# shield.net
KiCad netlist of a schematic drawn in EAGLE
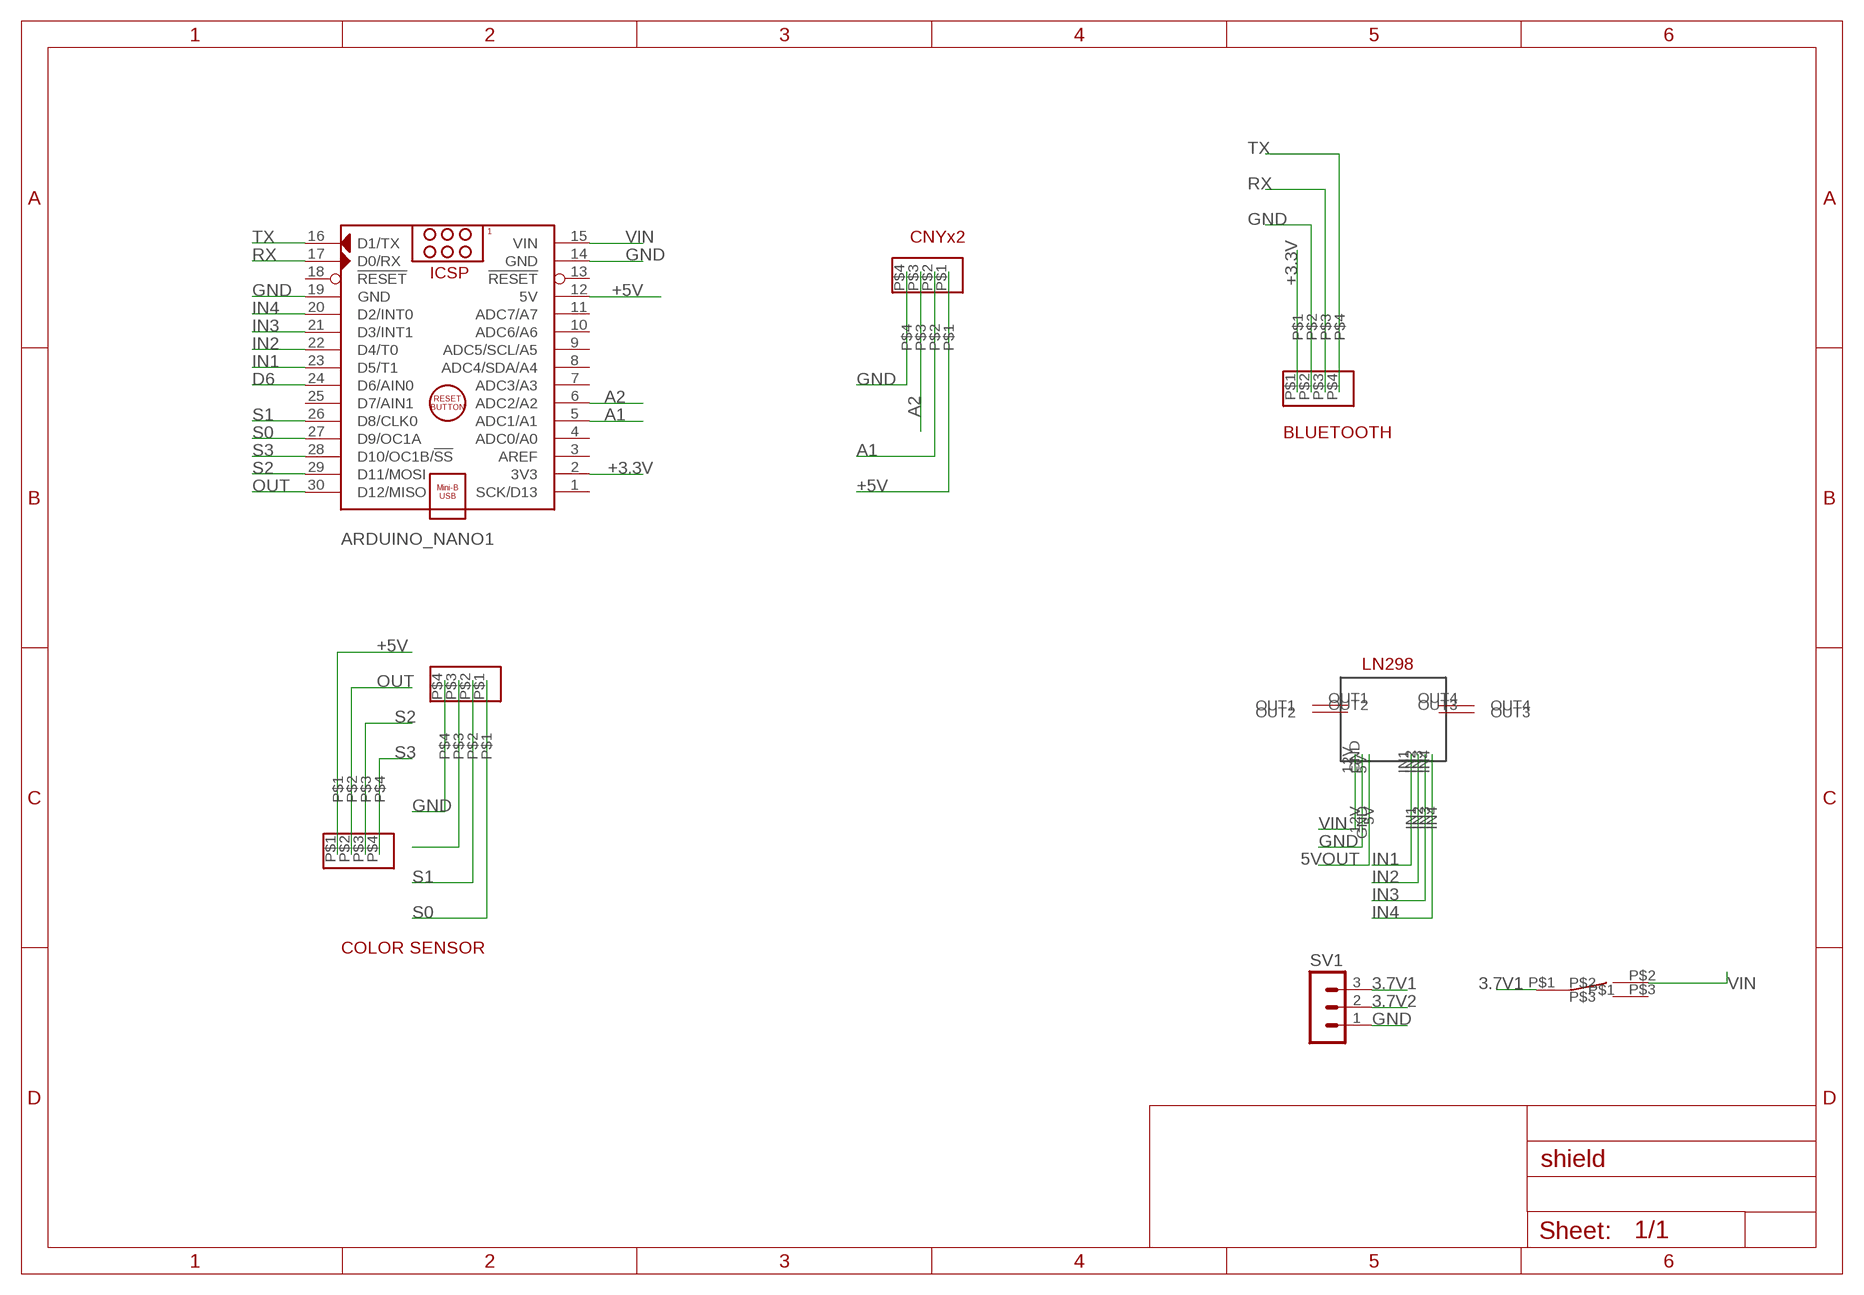
[diagram p0: schematic, sheet 1]

(export (version "E")
  (design (tool "Eeschema 10.0.6"))
  (components
    (comp (ref "ARDUINO_NANO1")
      (value "ARDUINO_NANO")
      (footprint "eagle-import:ARDUINO_NANO")
      (libsource (lib "eagle-import") (part "ARDUINO_NANO"))
    )
    (comp (ref "SV1")
      (value "MA03-1")
      (footprint "eagle-import:MA03-1")
      (libsource (lib "eagle-import") (part "MA03-1"))
    )
    (comp (ref "U$1")
      (value "PIN4")
      (footprint "eagle-import:PIN4")
      (libsource (lib "eagle-import") (part "PIN4"))
    )
    (comp (ref "U$2")
      (value "PIN4")
      (footprint "eagle-import:PIN4")
      (libsource (lib "eagle-import") (part "PIN4"))
    )
    (comp (ref "U$3")
      (value "INTERRUPTOR")
      (footprint "eagle-import:INTERRUPTOR")
      (libsource (lib "eagle-import") (part "INTERRUPTOR"))
    )
    (comp (ref "U$4")
      (value "PIN4")
      (footprint "eagle-import:PIN4")
      (libsource (lib "eagle-import") (part "PIN4"))
    )
    (comp (ref "U$5")
      (value "LN298V2")
      (footprint "eagle-import:LN298V2")
      (libsource (lib "eagle-import") (part "LN298V2"))
    )
    (comp (ref "U$6")
      (value "PIN4")
      (footprint "eagle-import:PIN4")
      (libsource (lib "eagle-import") (part "PIN4"))
    )
  )
  (nets
    (net (code "1") (name "/+3.3V") (class "Default")
      (node (ref "ARDUINO_NANO1") (pin "2") (pinfunction "3V3_2") (pintype "output"))
      (node (ref "U$1") (pin "P$1") (pinfunction "P$1_P$1") (pintype "bidirectional"))
    )
    (net (code "2") (name "/+5V") (class "Default")
      (node (ref "ARDUINO_NANO1") (pin "12") (pinfunction "5V_12") (pintype "power_in"))
      (node (ref "U$2") (pin "P$1") (pinfunction "P$1_P$1") (pintype "bidirectional"))
      (node (ref "U$6") (pin "P$1") (pinfunction "P$1_P$1") (pintype "bidirectional"))
    )
    (net (code "3") (name "/3.7V1") (class "Default")
      (node (ref "SV1") (pin "3") (pinfunction "3_3") (pintype "passive"))
      (node (ref "U$3") (pin "P$1") (pinfunction "P$1_P$1") (pintype "bidirectional"))
    )
    (net (code "4") (name "/3.7V2") (class "Default")
      (node (ref "SV1") (pin "2") (pinfunction "2_2") (pintype "passive"))
    )
    (net (code "5") (name "/5VOUT") (class "Default")
      (node (ref "U$5") (pin "5V") (pinfunction "5V_5V") (pintype "bidirectional"))
    )
    (net (code "6") (name "/A1") (class "Default")
      (node (ref "ARDUINO_NANO1") (pin "5") (pinfunction "ADC1/A1_5") (pintype "bidirectional"))
      (node (ref "U$6") (pin "P$2") (pinfunction "P$2_P$2") (pintype "bidirectional"))
    )
    (net (code "7") (name "/A2") (class "Default")
      (node (ref "ARDUINO_NANO1") (pin "6") (pinfunction "ADC2/A2_6") (pintype "bidirectional"))
      (node (ref "U$6") (pin "P$3") (pinfunction "P$3_P$3") (pintype "bidirectional"))
    )
    (net (code "8") (name "/D6") (class "Default")
      (node (ref "ARDUINO_NANO1") (pin "24") (pinfunction "D6/AIN0_24") (pintype "bidirectional"))
    )
    (net (code "9") (name "/GND") (class "Default")
      (node (ref "ARDUINO_NANO1") (pin "14") (pinfunction "GND_14") (pintype "power_in"))
      (node (ref "ARDUINO_NANO1") (pin "19") (pinfunction "GND_19") (pintype "power_in"))
      (node (ref "SV1") (pin "1") (pinfunction "1_1") (pintype "passive"))
      (node (ref "U$1") (pin "P$2") (pinfunction "P$2_P$2") (pintype "bidirectional"))
      (node (ref "U$4") (pin "P$4") (pinfunction "P$4_P$4") (pintype "bidirectional"))
      (node (ref "U$5") (pin "GND") (pinfunction "GND_GND") (pintype "bidirectional"))
      (node (ref "U$6") (pin "P$4") (pinfunction "P$4_P$4") (pintype "bidirectional"))
    )
    (net (code "10") (name "/IN1") (class "Default")
      (node (ref "ARDUINO_NANO1") (pin "23") (pinfunction "D5/T1_23") (pintype "bidirectional"))
      (node (ref "U$5") (pin "IN1") (pinfunction "IN1_IN1") (pintype "bidirectional"))
    )
    (net (code "11") (name "/IN2") (class "Default")
      (node (ref "ARDUINO_NANO1") (pin "22") (pinfunction "D4/T0_22") (pintype "bidirectional"))
      (node (ref "U$5") (pin "IN2") (pinfunction "IN2_IN2") (pintype "bidirectional"))
    )
    (net (code "12") (name "/IN3") (class "Default")
      (node (ref "ARDUINO_NANO1") (pin "21") (pinfunction "D3/INT1_21") (pintype "bidirectional"))
      (node (ref "U$5") (pin "IN3") (pinfunction "IN3_IN3") (pintype "bidirectional"))
    )
    (net (code "13") (name "/IN4") (class "Default")
      (node (ref "ARDUINO_NANO1") (pin "20") (pinfunction "D2/INT0_20") (pintype "bidirectional"))
      (node (ref "U$5") (pin "IN4") (pinfunction "IN4_IN4") (pintype "bidirectional"))
    )
    (net (code "14") (name "/OUT") (class "Default")
      (node (ref "ARDUINO_NANO1") (pin "30") (pinfunction "D12/MISO_30") (pintype "bidirectional"))
      (node (ref "U$2") (pin "P$2") (pinfunction "P$2_P$2") (pintype "bidirectional"))
    )
    (net (code "15") (name "/RX") (class "Default")
      (node (ref "ARDUINO_NANO1") (pin "17") (pinfunction "D0/RX_17") (pintype "bidirectional"))
      (node (ref "U$1") (pin "P$3") (pinfunction "P$3_P$3") (pintype "bidirectional"))
    )
    (net (code "16") (name "/S0") (class "Default")
      (node (ref "ARDUINO_NANO1") (pin "27") (pinfunction "D9/OC1A_27") (pintype "bidirectional"))
      (node (ref "U$4") (pin "P$1") (pinfunction "P$1_P$1") (pintype "bidirectional"))
    )
    (net (code "17") (name "/S1") (class "Default")
      (node (ref "ARDUINO_NANO1") (pin "26") (pinfunction "D8/CLK0_26") (pintype "bidirectional"))
      (node (ref "U$4") (pin "P$2") (pinfunction "P$2_P$2") (pintype "bidirectional"))
    )
    (net (code "18") (name "/S2") (class "Default")
      (node (ref "ARDUINO_NANO1") (pin "29") (pinfunction "D11/MOSI_29") (pintype "bidirectional"))
      (node (ref "U$2") (pin "P$3") (pinfunction "P$3_P$3") (pintype "bidirectional"))
    )
    (net (code "19") (name "/S3") (class "Default")
      (node (ref "ARDUINO_NANO1") (pin "28") (pinfunction "D10/OC1B/~{SS}_28") (pintype "bidirectional"))
      (node (ref "U$2") (pin "P$4") (pinfunction "P$4_P$4") (pintype "bidirectional"))
    )
    (net (code "20") (name "/TX") (class "Default")
      (node (ref "ARDUINO_NANO1") (pin "16") (pinfunction "D1/TX_16") (pintype "bidirectional"))
      (node (ref "U$1") (pin "P$4") (pinfunction "P$4_P$4") (pintype "bidirectional"))
    )
    (net (code "21") (name "/VIN") (class "Default")
      (node (ref "ARDUINO_NANO1") (pin "15") (pinfunction "VIN_15") (pintype "power_in"))
      (node (ref "U$3") (pin "P$2") (pinfunction "P$2_P$2") (pintype "bidirectional"))
      (node (ref "U$5") (pin "12V") (pinfunction "12V_12V") (pintype "bidirectional"))
    )
    (net (code "22") (name "unconnected-(ARDUINO_NANO1-ADC0{slash}A0-Pad4)") (class "Default")
      (node (ref "ARDUINO_NANO1") (pin "4") (pinfunction "ADC0/A0_4") (pintype "bidirectional"))
    )
    (net (code "23") (name "unconnected-(ARDUINO_NANO1-ADC3{slash}A3-Pad7)") (class "Default")
      (node (ref "ARDUINO_NANO1") (pin "7") (pinfunction "ADC3/A3_7") (pintype "bidirectional"))
    )
    (net (code "24") (name "unconnected-(ARDUINO_NANO1-ADC4{slash}SDA{slash}A4-Pad8)") (class "Default")
      (node (ref "ARDUINO_NANO1") (pin "8") (pinfunction "ADC4/SDA/A4_8") (pintype "bidirectional"))
    )
    (net (code "25") (name "unconnected-(ARDUINO_NANO1-ADC5{slash}SCL{slash}A5-Pad9)") (class "Default")
      (node (ref "ARDUINO_NANO1") (pin "9") (pinfunction "ADC5/SCL/A5_9") (pintype "bidirectional"))
    )
    (net (code "26") (name "unconnected-(ARDUINO_NANO1-ADC6{slash}A6-Pad10)") (class "Default")
      (node (ref "ARDUINO_NANO1") (pin "10") (pinfunction "ADC6/A6_10") (pintype "bidirectional"))
    )
    (net (code "27") (name "unconnected-(ARDUINO_NANO1-ADC7{slash}A7-Pad11)") (class "Default")
      (node (ref "ARDUINO_NANO1") (pin "11") (pinfunction "ADC7/A7_11") (pintype "bidirectional"))
    )
    (net (code "28") (name "unconnected-(ARDUINO_NANO1-AREF-Pad3)") (class "Default")
      (node (ref "ARDUINO_NANO1") (pin "3") (pinfunction "AREF_3") (pintype "input"))
    )
    (net (code "29") (name "unconnected-(ARDUINO_NANO1-D7{slash}AIN1-Pad25)") (class "Default")
      (node (ref "ARDUINO_NANO1") (pin "25") (pinfunction "D7/AIN1_25") (pintype "bidirectional"))
    )
    (net (code "30") (name "unconnected-(ARDUINO_NANO1-SCK{slash}D13-Pad1)") (class "Default")
      (node (ref "ARDUINO_NANO1") (pin "1") (pinfunction "SCK/D13_1") (pintype "bidirectional"))
    )
    (net (code "31") (name "unconnected-(ARDUINO_NANO1-~{RESET}-Pad13)") (class "Default")
      (node (ref "ARDUINO_NANO1") (pin "13") (pinfunction "~{RESET}_13") (pintype "input"))
    )
    (net (code "32") (name "unconnected-(ARDUINO_NANO1-~{RESET}-Pad18)") (class "Default")
      (node (ref "ARDUINO_NANO1") (pin "18") (pinfunction "~{RESET}_18") (pintype "input"))
    )
    (net (code "33") (name "unconnected-(U$3-PadP$3)") (class "Default")
      (node (ref "U$3") (pin "P$3") (pinfunction "P$3_P$3") (pintype "bidirectional"))
    )
    (net (code "34") (name "unconnected-(U$4-PadP$3)") (class "Default")
      (node (ref "U$4") (pin "P$3") (pinfunction "P$3_P$3") (pintype "bidirectional"))
    )
    (net (code "35") (name "unconnected-(U$5-PadOUT1)") (class "Default")
      (node (ref "U$5") (pin "OUT1") (pinfunction "OUT1_OUT1") (pintype "bidirectional"))
    )
    (net (code "36") (name "unconnected-(U$5-PadOUT2)") (class "Default")
      (node (ref "U$5") (pin "OUT2") (pinfunction "OUT2_OUT2") (pintype "bidirectional"))
    )
    (net (code "37") (name "unconnected-(U$5-PadOUT3)") (class "Default")
      (node (ref "U$5") (pin "OUT3") (pinfunction "OUT3_OUT3") (pintype "bidirectional"))
    )
    (net (code "38") (name "unconnected-(U$5-PadOUT4)") (class "Default")
      (node (ref "U$5") (pin "OUT4") (pinfunction "OUT4_OUT4") (pintype "bidirectional"))
    )
  )
)
